# Steering_Wheel_LED_Right.net
KiCad netlist of a schematic drawn in EAGLE
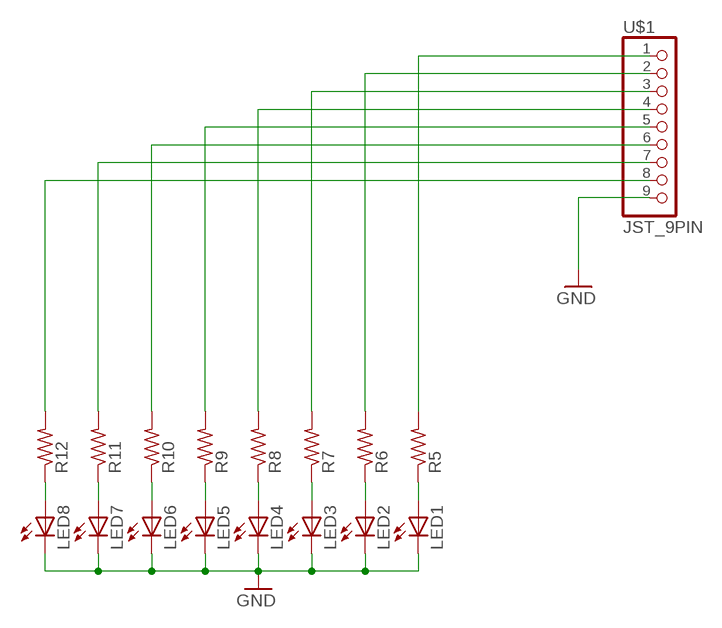
[diagram p0: schematic, sheet 1]

(export (version "E")
  (design (tool "Eeschema 10.0.6"))
  (components
    (comp (ref "LED1")
      (value "LED3MM")
      (footprint "eagle-import:LED3MM")
      (libsource (lib "eagle-import") (part "LED3MM"))
    )
    (comp (ref "LED2")
      (value "LED3MM")
      (footprint "eagle-import:LED3MM")
      (libsource (lib "eagle-import") (part "LED3MM"))
    )
    (comp (ref "LED3")
      (value "LED3MM")
      (footprint "eagle-import:LED3MM")
      (libsource (lib "eagle-import") (part "LED3MM"))
    )
    (comp (ref "LED4")
      (value "LED3MM")
      (footprint "eagle-import:LED3MM")
      (libsource (lib "eagle-import") (part "LED3MM"))
    )
    (comp (ref "LED5")
      (value "LED3MM")
      (footprint "eagle-import:LED3MM")
      (libsource (lib "eagle-import") (part "LED3MM"))
    )
    (comp (ref "LED6")
      (value "LED3MM")
      (footprint "eagle-import:LED3MM")
      (libsource (lib "eagle-import") (part "LED3MM"))
    )
    (comp (ref "LED7")
      (value "LED3MM")
      (footprint "eagle-import:LED3MM")
      (libsource (lib "eagle-import") (part "LED3MM"))
    )
    (comp (ref "LED8")
      (value "LED3MM")
      (footprint "eagle-import:LED3MM")
      (libsource (lib "eagle-import") (part "LED3MM"))
    )
    (comp (ref "R5")
      (value "R-US_M1206")
      (footprint "eagle-import:M1206")
      (libsource (lib "eagle-import") (part "R-US_M1206"))
    )
    (comp (ref "R6")
      (value "R-US_M1206")
      (footprint "eagle-import:M1206")
      (libsource (lib "eagle-import") (part "R-US_M1206"))
    )
    (comp (ref "R7")
      (value "R-US_M1206")
      (footprint "eagle-import:M1206")
      (libsource (lib "eagle-import") (part "R-US_M1206"))
    )
    (comp (ref "R8")
      (value "R-US_M1206")
      (footprint "eagle-import:M1206")
      (libsource (lib "eagle-import") (part "R-US_M1206"))
    )
    (comp (ref "R9")
      (value "R-US_M1206")
      (footprint "eagle-import:M1206")
      (libsource (lib "eagle-import") (part "R-US_M1206"))
    )
    (comp (ref "R10")
      (value "R-US_M1206")
      (footprint "eagle-import:M1206")
      (libsource (lib "eagle-import") (part "R-US_M1206"))
    )
    (comp (ref "R11")
      (value "R-US_M1206")
      (footprint "eagle-import:M1206")
      (libsource (lib "eagle-import") (part "R-US_M1206"))
    )
    (comp (ref "R12")
      (value "R-US_M1206")
      (footprint "eagle-import:M1206")
      (libsource (lib "eagle-import") (part "R-US_M1206"))
    )
    (comp (ref "U$1")
      (value "JST_9PIN")
      (footprint "eagle-import:JST-PH-9-THM")
      (libsource (lib "eagle-import") (part "JST_9PIN"))
    )
  )
  (nets
    (net (code "1") (name "GND") (class "Default")
      (node (ref "LED1") (pin "K") (pinfunction "C_K") (pintype "passive"))
      (node (ref "LED2") (pin "K") (pinfunction "C_K") (pintype "passive"))
      (node (ref "LED3") (pin "K") (pinfunction "C_K") (pintype "passive"))
      (node (ref "LED4") (pin "K") (pinfunction "C_K") (pintype "passive"))
      (node (ref "LED5") (pin "K") (pinfunction "C_K") (pintype "passive"))
      (node (ref "LED6") (pin "K") (pinfunction "C_K") (pintype "passive"))
      (node (ref "LED7") (pin "K") (pinfunction "C_K") (pintype "passive"))
      (node (ref "LED8") (pin "K") (pinfunction "C_K") (pintype "passive"))
      (node (ref "U$1") (pin "9") (pinfunction "9_9") (pintype "passive"))
    )
    (net (code "2") (name "Net-(LED1-PadA)") (class "Default")
      (node (ref "LED1") (pin "A") (pinfunction "A_A") (pintype "passive"))
      (node (ref "R5") (pin "1") (pinfunction "1_1") (pintype "passive"))
    )
    (net (code "3") (name "Net-(LED2-PadA)") (class "Default")
      (node (ref "LED2") (pin "A") (pinfunction "A_A") (pintype "passive"))
      (node (ref "R6") (pin "1") (pinfunction "1_1") (pintype "passive"))
    )
    (net (code "4") (name "Net-(LED3-PadA)") (class "Default")
      (node (ref "LED3") (pin "A") (pinfunction "A_A") (pintype "passive"))
      (node (ref "R7") (pin "1") (pinfunction "1_1") (pintype "passive"))
    )
    (net (code "5") (name "Net-(LED4-PadA)") (class "Default")
      (node (ref "LED4") (pin "A") (pinfunction "A_A") (pintype "passive"))
      (node (ref "R8") (pin "1") (pinfunction "1_1") (pintype "passive"))
    )
    (net (code "6") (name "Net-(LED5-PadA)") (class "Default")
      (node (ref "LED5") (pin "A") (pinfunction "A_A") (pintype "passive"))
      (node (ref "R9") (pin "1") (pinfunction "1_1") (pintype "passive"))
    )
    (net (code "7") (name "Net-(LED6-PadA)") (class "Default")
      (node (ref "LED6") (pin "A") (pinfunction "A_A") (pintype "passive"))
      (node (ref "R10") (pin "1") (pinfunction "1_1") (pintype "passive"))
    )
    (net (code "8") (name "Net-(LED7-PadA)") (class "Default")
      (node (ref "LED7") (pin "A") (pinfunction "A_A") (pintype "passive"))
      (node (ref "R11") (pin "1") (pinfunction "1_1") (pintype "passive"))
    )
    (net (code "9") (name "Net-(LED8-PadA)") (class "Default")
      (node (ref "LED8") (pin "A") (pinfunction "A_A") (pintype "passive"))
      (node (ref "R12") (pin "1") (pinfunction "1_1") (pintype "passive"))
    )
    (net (code "10") (name "Net-(R5-Pad2)") (class "Default")
      (node (ref "R5") (pin "2") (pinfunction "2_2") (pintype "passive"))
      (node (ref "U$1") (pin "1") (pinfunction "1_1") (pintype "passive"))
    )
    (net (code "11") (name "Net-(R6-Pad2)") (class "Default")
      (node (ref "R6") (pin "2") (pinfunction "2_2") (pintype "passive"))
      (node (ref "U$1") (pin "2") (pinfunction "2_2") (pintype "passive"))
    )
    (net (code "12") (name "Net-(R7-Pad2)") (class "Default")
      (node (ref "R7") (pin "2") (pinfunction "2_2") (pintype "passive"))
      (node (ref "U$1") (pin "3") (pinfunction "3_3") (pintype "passive"))
    )
    (net (code "13") (name "Net-(R8-Pad2)") (class "Default")
      (node (ref "R8") (pin "2") (pinfunction "2_2") (pintype "passive"))
      (node (ref "U$1") (pin "4") (pinfunction "4_4") (pintype "passive"))
    )
    (net (code "14") (name "Net-(R9-Pad2)") (class "Default")
      (node (ref "R9") (pin "2") (pinfunction "2_2") (pintype "passive"))
      (node (ref "U$1") (pin "5") (pinfunction "5_5") (pintype "passive"))
    )
    (net (code "15") (name "Net-(R10-Pad2)") (class "Default")
      (node (ref "R10") (pin "2") (pinfunction "2_2") (pintype "passive"))
      (node (ref "U$1") (pin "6") (pinfunction "6_6") (pintype "passive"))
    )
    (net (code "16") (name "Net-(R11-Pad2)") (class "Default")
      (node (ref "R11") (pin "2") (pinfunction "2_2") (pintype "passive"))
      (node (ref "U$1") (pin "7") (pinfunction "7_7") (pintype "passive"))
    )
    (net (code "17") (name "Net-(R12-Pad2)") (class "Default")
      (node (ref "R12") (pin "2") (pinfunction "2_2") (pintype "passive"))
      (node (ref "U$1") (pin "8") (pinfunction "8_8") (pintype "passive"))
    )
  )
)
